# CodeCard_002.net
KiCad netlist of a schematic drawn in EAGLE
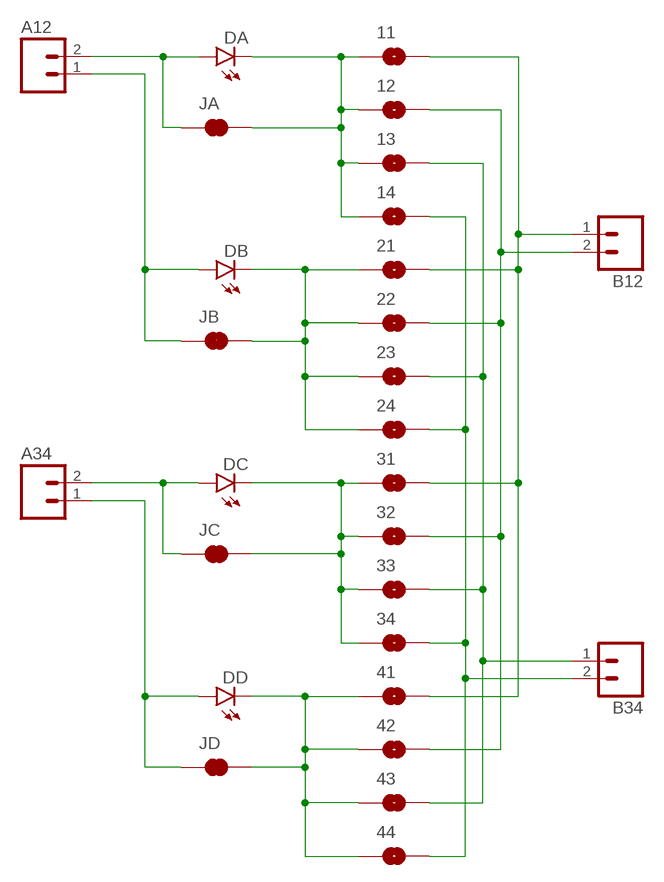
[diagram p0: schematic, sheet 1]

(export (version "E")
  (design (tool "Eeschema 10.0.6"))
  (components
    (comp (ref "11")
      (value "JUMPER-PAD-2-NOROUND")
      (footprint "eagle-import:PAD-JUMPER-2-NO_YES_SILK_ROUND")
      (libsource (lib "eagle-import") (part "JUMPER-PAD-2-NOROUND"))
    )
    (comp (ref "12")
      (value "JUMPER-PAD-2-NOROUND")
      (footprint "eagle-import:PAD-JUMPER-2-NO_YES_SILK_ROUND")
      (libsource (lib "eagle-import") (part "JUMPER-PAD-2-NOROUND"))
    )
    (comp (ref "13")
      (value "JUMPER-PAD-2-NOROUND")
      (footprint "eagle-import:PAD-JUMPER-2-NO_YES_SILK_ROUND")
      (libsource (lib "eagle-import") (part "JUMPER-PAD-2-NOROUND"))
    )
    (comp (ref "14")
      (value "JUMPER-PAD-2-NOROUND")
      (footprint "eagle-import:PAD-JUMPER-2-NO_YES_SILK_ROUND")
      (libsource (lib "eagle-import") (part "JUMPER-PAD-2-NOROUND"))
    )
    (comp (ref "21")
      (value "JUMPER-PAD-2-NOROUND")
      (footprint "eagle-import:PAD-JUMPER-2-NO_YES_SILK_ROUND")
      (libsource (lib "eagle-import") (part "JUMPER-PAD-2-NOROUND"))
    )
    (comp (ref "22")
      (value "JUMPER-PAD-2-NOROUND")
      (footprint "eagle-import:PAD-JUMPER-2-NO_YES_SILK_ROUND")
      (libsource (lib "eagle-import") (part "JUMPER-PAD-2-NOROUND"))
    )
    (comp (ref "23")
      (value "JUMPER-PAD-2-NOROUND")
      (footprint "eagle-import:PAD-JUMPER-2-NO_YES_SILK_ROUND")
      (libsource (lib "eagle-import") (part "JUMPER-PAD-2-NOROUND"))
    )
    (comp (ref "24")
      (value "JUMPER-PAD-2-NOROUND")
      (footprint "eagle-import:PAD-JUMPER-2-NO_YES_SILK_ROUND")
      (libsource (lib "eagle-import") (part "JUMPER-PAD-2-NOROUND"))
    )
    (comp (ref "31")
      (value "JUMPER-PAD-2-NOROUND")
      (footprint "eagle-import:PAD-JUMPER-2-NO_YES_SILK_ROUND")
      (libsource (lib "eagle-import") (part "JUMPER-PAD-2-NOROUND"))
    )
    (comp (ref "32")
      (value "JUMPER-PAD-2-NOROUND")
      (footprint "eagle-import:PAD-JUMPER-2-NO_YES_SILK_ROUND")
      (libsource (lib "eagle-import") (part "JUMPER-PAD-2-NOROUND"))
    )
    (comp (ref "33")
      (value "JUMPER-PAD-2-NOROUND")
      (footprint "eagle-import:PAD-JUMPER-2-NO_YES_SILK_ROUND")
      (libsource (lib "eagle-import") (part "JUMPER-PAD-2-NOROUND"))
    )
    (comp (ref "34")
      (value "JUMPER-PAD-2-NOROUND")
      (footprint "eagle-import:PAD-JUMPER-2-NO_YES_SILK_ROUND")
      (libsource (lib "eagle-import") (part "JUMPER-PAD-2-NOROUND"))
    )
    (comp (ref "41")
      (value "JUMPER-PAD-2-NOROUND")
      (footprint "eagle-import:PAD-JUMPER-2-NO_YES_SILK_ROUND")
      (libsource (lib "eagle-import") (part "JUMPER-PAD-2-NOROUND"))
    )
    (comp (ref "42")
      (value "JUMPER-PAD-2-NOROUND")
      (footprint "eagle-import:PAD-JUMPER-2-NO_YES_SILK_ROUND")
      (libsource (lib "eagle-import") (part "JUMPER-PAD-2-NOROUND"))
    )
    (comp (ref "43")
      (value "JUMPER-PAD-2-NOROUND")
      (footprint "eagle-import:PAD-JUMPER-2-NO_YES_SILK_ROUND")
      (libsource (lib "eagle-import") (part "JUMPER-PAD-2-NOROUND"))
    )
    (comp (ref "44")
      (value "JUMPER-PAD-2-NOROUND")
      (footprint "eagle-import:PAD-JUMPER-2-NO_YES_SILK_ROUND")
      (libsource (lib "eagle-import") (part "JUMPER-PAD-2-NOROUND"))
    )
    (comp (ref "A12")
      (value "M02PTH3")
      (footprint "eagle-import:1X02_LONGPADS")
      (libsource (lib "eagle-import") (part "M02PTH3"))
    )
    (comp (ref "A34")
      (value "M02PTH3")
      (footprint "eagle-import:1X02_LONGPADS")
      (libsource (lib "eagle-import") (part "M02PTH3"))
    )
    (comp (ref "B12")
      (value "M02PTH3")
      (footprint "eagle-import:1X02_LONGPADS")
      (libsource (lib "eagle-import") (part "M02PTH3"))
    )
    (comp (ref "B34")
      (value "M02PTH3")
      (footprint "eagle-import:1X02_LONGPADS")
      (libsource (lib "eagle-import") (part "M02PTH3"))
    )
    (comp (ref "DA")
      (value "LED1206")
      (footprint "eagle-import:LED-1206")
      (libsource (lib "eagle-import") (part "LED1206"))
    )
    (comp (ref "DB")
      (value "LED1206")
      (footprint "eagle-import:LED-1206")
      (libsource (lib "eagle-import") (part "LED1206"))
    )
    (comp (ref "DC")
      (value "LED1206")
      (footprint "eagle-import:LED-1206")
      (libsource (lib "eagle-import") (part "LED1206"))
    )
    (comp (ref "DD")
      (value "LED1206")
      (footprint "eagle-import:LED-1206")
      (libsource (lib "eagle-import") (part "LED1206"))
    )
    (comp (ref "JA")
      (value "JUMPER-PAD-2-NC_BY_TRACENO_SILK")
      (footprint "eagle-import:PAD-JUMPER-2-NC_BY_TRACE_NO_SILK")
      (libsource (lib "eagle-import") (part "JUMPER-PAD-2-NC_BY_TRACENO_SILK"))
    )
    (comp (ref "JB")
      (value "JUMPER-PAD-2-NC_BY_TRACENO_SILK")
      (footprint "eagle-import:PAD-JUMPER-2-NC_BY_TRACE_NO_SILK")
      (libsource (lib "eagle-import") (part "JUMPER-PAD-2-NC_BY_TRACENO_SILK"))
    )
    (comp (ref "JC")
      (value "JUMPER-PAD-2-NC_BY_TRACENO_SILK")
      (footprint "eagle-import:PAD-JUMPER-2-NC_BY_TRACE_NO_SILK")
      (libsource (lib "eagle-import") (part "JUMPER-PAD-2-NC_BY_TRACENO_SILK"))
    )
    (comp (ref "JD")
      (value "JUMPER-PAD-2-NC_BY_TRACENO_SILK")
      (footprint "eagle-import:PAD-JUMPER-2-NC_BY_TRACE_NO_SILK")
      (libsource (lib "eagle-import") (part "JUMPER-PAD-2-NC_BY_TRACENO_SILK"))
    )
  )
  (nets
    (net (code "1") (name "Net-(11-Pad1)") (class "Default")
      (node (ref "11") (pin "1") (pinfunction "1_1") (pintype "passive"))
      (node (ref "12") (pin "1") (pinfunction "1_1") (pintype "passive"))
      (node (ref "13") (pin "1") (pinfunction "1_1") (pintype "passive"))
      (node (ref "14") (pin "1") (pinfunction "1_1") (pintype "passive"))
      (node (ref "DA") (pin "C") (pinfunction "C_C") (pintype "passive"))
      (node (ref "JA") (pin "2") (pinfunction "2_2") (pintype "passive"))
    )
    (net (code "2") (name "Net-(11-Pad2)") (class "Default")
      (node (ref "11") (pin "2") (pinfunction "2_2") (pintype "passive"))
      (node (ref "21") (pin "2") (pinfunction "2_2") (pintype "passive"))
      (node (ref "31") (pin "2") (pinfunction "2_2") (pintype "passive"))
      (node (ref "41") (pin "2") (pinfunction "2_2") (pintype "passive"))
      (node (ref "B12") (pin "1") (pinfunction "1_1") (pintype "passive"))
    )
    (net (code "3") (name "Net-(12-Pad2)") (class "Default")
      (node (ref "12") (pin "2") (pinfunction "2_2") (pintype "passive"))
      (node (ref "22") (pin "2") (pinfunction "2_2") (pintype "passive"))
      (node (ref "32") (pin "2") (pinfunction "2_2") (pintype "passive"))
      (node (ref "42") (pin "2") (pinfunction "2_2") (pintype "passive"))
      (node (ref "B12") (pin "2") (pinfunction "2_2") (pintype "passive"))
    )
    (net (code "4") (name "Net-(13-Pad2)") (class "Default")
      (node (ref "13") (pin "2") (pinfunction "2_2") (pintype "passive"))
      (node (ref "23") (pin "2") (pinfunction "2_2") (pintype "passive"))
      (node (ref "33") (pin "2") (pinfunction "2_2") (pintype "passive"))
      (node (ref "43") (pin "2") (pinfunction "2_2") (pintype "passive"))
      (node (ref "B34") (pin "1") (pinfunction "1_1") (pintype "passive"))
    )
    (net (code "5") (name "Net-(14-Pad2)") (class "Default")
      (node (ref "14") (pin "2") (pinfunction "2_2") (pintype "passive"))
      (node (ref "24") (pin "2") (pinfunction "2_2") (pintype "passive"))
      (node (ref "34") (pin "2") (pinfunction "2_2") (pintype "passive"))
      (node (ref "44") (pin "2") (pinfunction "2_2") (pintype "passive"))
      (node (ref "B34") (pin "2") (pinfunction "2_2") (pintype "passive"))
    )
    (net (code "6") (name "Net-(21-Pad1)") (class "Default")
      (node (ref "21") (pin "1") (pinfunction "1_1") (pintype "passive"))
      (node (ref "22") (pin "1") (pinfunction "1_1") (pintype "passive"))
      (node (ref "23") (pin "1") (pinfunction "1_1") (pintype "passive"))
      (node (ref "24") (pin "1") (pinfunction "1_1") (pintype "passive"))
      (node (ref "DB") (pin "C") (pinfunction "C_C") (pintype "passive"))
      (node (ref "JB") (pin "2") (pinfunction "2_2") (pintype "passive"))
    )
    (net (code "7") (name "Net-(31-Pad1)") (class "Default")
      (node (ref "31") (pin "1") (pinfunction "1_1") (pintype "passive"))
      (node (ref "32") (pin "1") (pinfunction "1_1") (pintype "passive"))
      (node (ref "33") (pin "1") (pinfunction "1_1") (pintype "passive"))
      (node (ref "34") (pin "1") (pinfunction "1_1") (pintype "passive"))
      (node (ref "DC") (pin "C") (pinfunction "C_C") (pintype "passive"))
      (node (ref "JC") (pin "2") (pinfunction "2_2") (pintype "passive"))
    )
    (net (code "8") (name "Net-(41-Pad1)") (class "Default")
      (node (ref "41") (pin "1") (pinfunction "1_1") (pintype "passive"))
      (node (ref "42") (pin "1") (pinfunction "1_1") (pintype "passive"))
      (node (ref "43") (pin "1") (pinfunction "1_1") (pintype "passive"))
      (node (ref "44") (pin "1") (pinfunction "1_1") (pintype "passive"))
      (node (ref "DD") (pin "C") (pinfunction "C_C") (pintype "passive"))
      (node (ref "JD") (pin "2") (pinfunction "2_2") (pintype "passive"))
    )
    (net (code "9") (name "Net-(A12-Pad1)") (class "Default")
      (node (ref "A12") (pin "1") (pinfunction "1_1") (pintype "passive"))
      (node (ref "DB") (pin "A") (pinfunction "A_A") (pintype "passive"))
      (node (ref "JB") (pin "1") (pinfunction "1_1") (pintype "passive"))
    )
    (net (code "10") (name "Net-(A12-Pad2)") (class "Default")
      (node (ref "A12") (pin "2") (pinfunction "2_2") (pintype "passive"))
      (node (ref "DA") (pin "A") (pinfunction "A_A") (pintype "passive"))
      (node (ref "JA") (pin "1") (pinfunction "1_1") (pintype "passive"))
    )
    (net (code "11") (name "Net-(A34-Pad1)") (class "Default")
      (node (ref "A34") (pin "1") (pinfunction "1_1") (pintype "passive"))
      (node (ref "DD") (pin "A") (pinfunction "A_A") (pintype "passive"))
      (node (ref "JD") (pin "1") (pinfunction "1_1") (pintype "passive"))
    )
    (net (code "12") (name "Net-(A34-Pad2)") (class "Default")
      (node (ref "A34") (pin "2") (pinfunction "2_2") (pintype "passive"))
      (node (ref "DC") (pin "A") (pinfunction "A_A") (pintype "passive"))
      (node (ref "JC") (pin "1") (pinfunction "1_1") (pintype "passive"))
    )
  )
)
